# LCD_Connector.net
KiCad netlist of a schematic drawn in Altium Designer
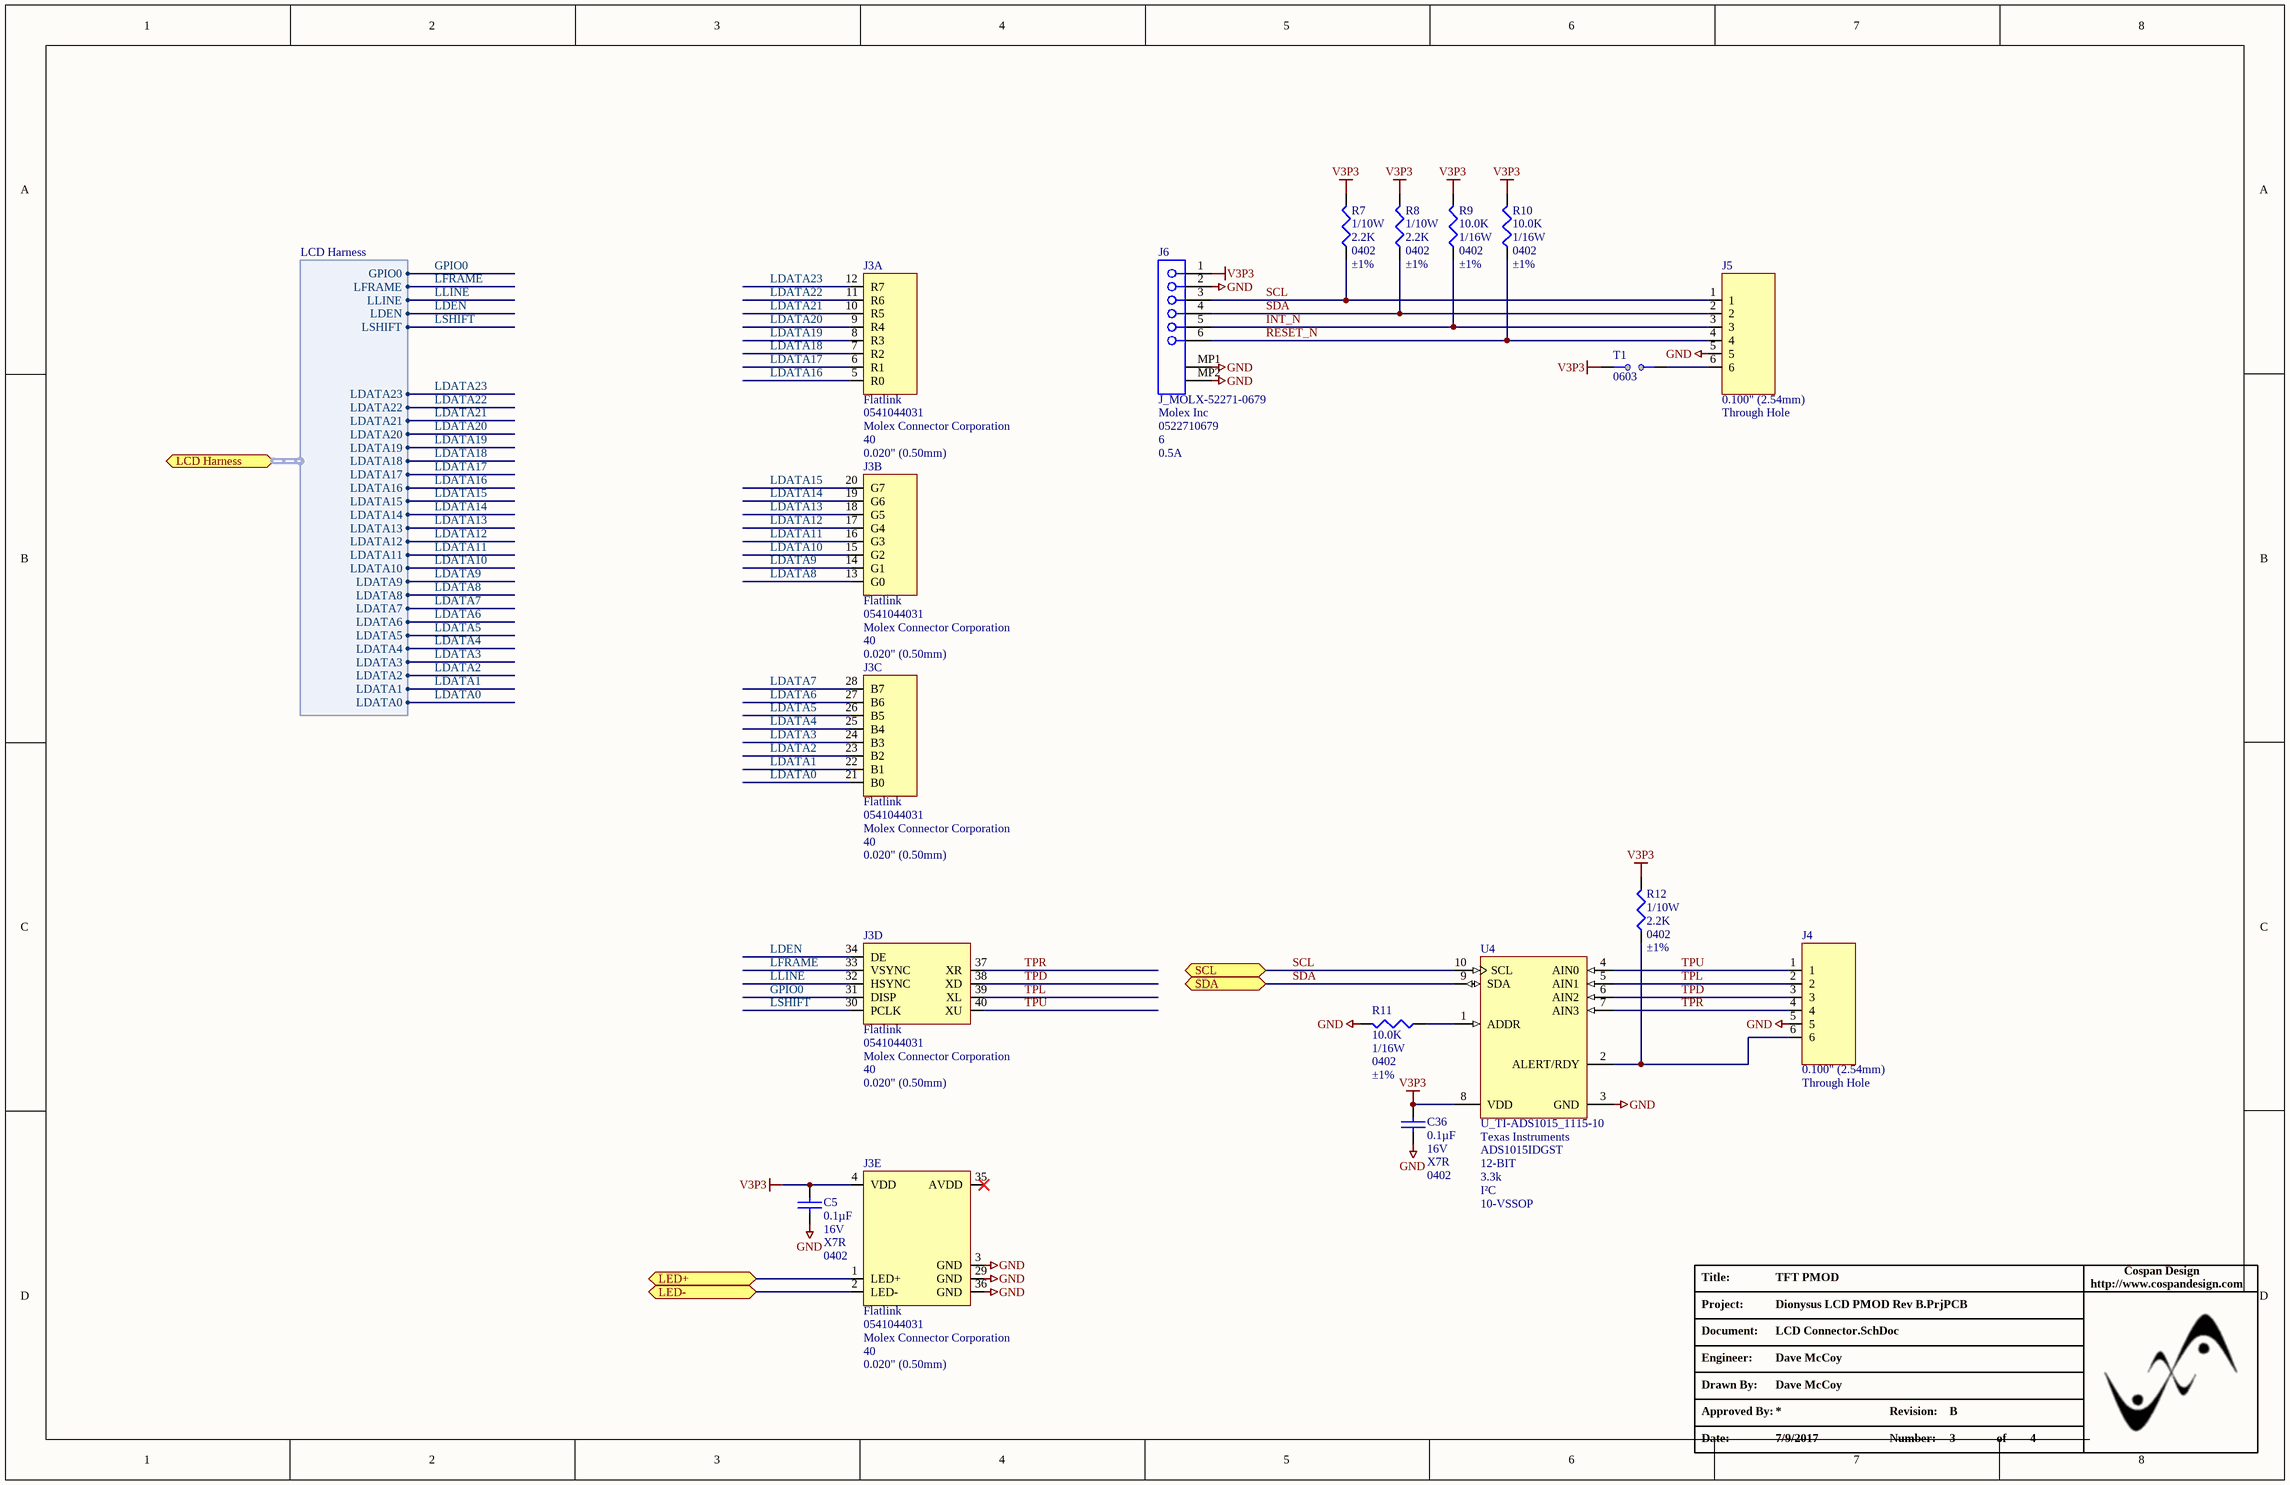
[diagram p0: LCD Connector.SchDoc]

(export (version "E")
  (design (tool "Eeschema 10.0.6"))
  (components
    (comp (ref "C5")
      (value "0.1uF")
      (footprint "C_0402")
      (description "CAP CER .10UF 16V X7R 0402")
      (fields
        (field (name "MANUFACTURER") "TDK Corporation")
        (field (name "MANUFACTURER PART NUMBER") "C1005X7R1C104K050BC")
        (field (name "CAPACITANCE") "0.1µF")
        (field (name "VOLTAGE - RATED") "16V")
        (field (name "TEMPERATURE COEFFICIENT") "X7R")
        (field (name "PACKAGE / CASE") "0402")
      )
      (libsource (lib "Main LibraryX") (part "C_0402_0.1UF_16V"))
    )
    (comp (ref "C36")
      (value "0.1uF")
      (footprint "C_0402")
      (description "CAP CER .10UF 16V X7R 0402")
      (fields
        (field (name "MANUFACTURER") "TDK Corporation")
        (field (name "MANUFACTURER PART NUMBER") "C1005X7R1C104K050BC")
        (field (name "CAPACITANCE") "0.1µF")
        (field (name "VOLTAGE - RATED") "16V")
        (field (name "TEMPERATURE COEFFICIENT") "X7R")
        (field (name "PACKAGE / CASE") "0402")
      )
      (libsource (lib "Main LibraryX") (part "C_0402_0.1UF_16V"))
    )
    (comp (ref "J3")
      (value "Flatlink")
      (footprint "FPC_40PIN")
      (description "CONN FFC/FPC .50MM 40POS R/A SMD")
      (fields
        (field (name "MANUFACTURER PART NUMBER") "0541044031")
        (field (name "MANUFACTURER") "Molex Connector Corporation")
        (field (name "NUMBER OF POSITIONS") "40")
        (field (name "PITCH") "0.020\" (0.50mm)")
      )
      (libsource (lib "Main LibraryX") (part "J_FPC_MOLEX_40POS_TOP"))
    )
    (comp (ref "J4")
      (value "J_HDR1X6_THRHOLE_VERT_FEMALE")
      (footprint "HDR_1X6 - FEMALE")
      (description "CONN HEADER FEMALE 6POS .1\" TIN")
      (fields
        (field (name "MANUFACTURER") "Samtec")
        (field (name "MANUFACTURER PART NUMBER") "SSW-106-01-T-S")
        (field (name "PITCH") "0.100\" (2.54mm)")
        (field (name "MOUNTING TYPE") "Through Hole")
      )
      (libsource (lib "Main Library") (part "J_HDR1X6_THRHOLE_VERT_FEMALE"))
    )
    (comp (ref "J5")
      (value "J_HDR1X6_THRHOLE_VERT")
      (footprint "HDR_1X6")
      (description "CONN HEADER .100\" 12POS TIN PCB")
      (fields
        (field (name "MANUFACTURER") "Samtec")
        (field (name "MANUFACTURER PART NUMBER") "TSW-106-07-T-S")
        (field (name "PITCH") "0.100\" (2.54mm)")
        (field (name "MOUNTING TYPE") "Through Hole")
      )
      (libsource (lib "Main Library") (part "J_HDR1X6_THRHOLE_VERT"))
    )
    (comp (ref "J6")
      (value "J_MOLX-52271-0679")
      (footprint "MOLX-52271-0679")
      (description "CONN FFC 6POS 1MM R/A ZIF SMD")
      (fields
        (field (name "MANUFACTURER") "Molex Inc")
        (field (name "MANUFACTURER PART NUMBER") "0522710679")
        (field (name "NUMBER OF POSITIONS") "6")
        (field (name "CURRENT RATING") "0.5A")
      )
      (libsource (lib "Main Library") (part "J_MOLX-52271-0679"))
    )
    (comp (ref "R7")
      (value "2.2k Ohms")
      (footprint "R_0402")
      (description "RES 2.20K OHM 1/10W 1% 0402 SMD")
      (fields
        (field (name "MANUFACTURER") "Yageo")
        (field (name "MANUFACTURER PART NUMBER") "RC0402FR-072K2L")
        (field (name "POWER (WATTS)") "1/10W")
        (field (name "RESISTANCE IN OHMS") "2.2K")
        (field (name "CASE") "0402")
        (field (name "TOLERANCE") "±1%")
      )
      (libsource (lib "Main Library") (part "R_0402_2.2K"))
    )
    (comp (ref "R8")
      (value "2.2k Ohms")
      (footprint "R_0402")
      (description "RES 2.20K OHM 1/10W 1% 0402 SMD")
      (fields
        (field (name "MANUFACTURER") "Yageo")
        (field (name "MANUFACTURER PART NUMBER") "RC0402FR-072K2L")
        (field (name "POWER (WATTS)") "1/10W")
        (field (name "RESISTANCE IN OHMS") "2.2K")
        (field (name "CASE") "0402")
        (field (name "TOLERANCE") "±1%")
      )
      (libsource (lib "Main Library") (part "R_0402_2.2K"))
    )
    (comp (ref "R9")
      (value "R_0402_10.0K")
      (footprint "R_0402")
      (description "RES 10.0K OHM 1/16W 1% 0402 SMD")
      (fields
        (field (name "MANUFACTURER") "Stackpole Electronics Inc")
        (field (name "MANUFACTURER PART NUMBER") "RMCF0402FT10K0")
        (field (name "RESISTANCE IN OHMS") "10.0K")
        (field (name "POWER (WATTS)") "1/16W")
        (field (name "CASE") "0402")
        (field (name "TOLERANCE") "±1%")
      )
      (libsource (lib "Cospan Design") (part "R_0402_10.0K"))
    )
    (comp (ref "R10")
      (value "R_0402_10.0K")
      (footprint "R_0402")
      (description "RES 10.0K OHM 1/16W 1% 0402 SMD")
      (fields
        (field (name "MANUFACTURER") "Stackpole Electronics Inc")
        (field (name "MANUFACTURER PART NUMBER") "RMCF0402FT10K0")
        (field (name "RESISTANCE IN OHMS") "10.0K")
        (field (name "POWER (WATTS)") "1/16W")
        (field (name "CASE") "0402")
        (field (name "TOLERANCE") "±1%")
      )
      (libsource (lib "Cospan Design") (part "R_0402_10.0K"))
    )
    (comp (ref "R11")
      (value "R_0402_10.0K")
      (footprint "R_0402")
      (description "RES 10.0K OHM 1/16W 1% 0402 SMD")
      (fields
        (field (name "MANUFACTURER") "Stackpole Electronics Inc")
        (field (name "MANUFACTURER PART NUMBER") "RMCF0402FT10K0")
        (field (name "RESISTANCE IN OHMS") "10.0K")
        (field (name "POWER (WATTS)") "1/16W")
        (field (name "CASE") "0402")
        (field (name "TOLERANCE") "±1%")
      )
      (libsource (lib "Cospan Design") (part "R_0402_10.0K"))
    )
    (comp (ref "R12")
      (value "2.2k Ohms")
      (footprint "R_0402")
      (description "RES 2.20K OHM 1/10W 1% 0402 SMD")
      (fields
        (field (name "MANUFACTURER") "Yageo")
        (field (name "MANUFACTURER PART NUMBER") "RC0402FR-072K2L")
        (field (name "POWER (WATTS)") "1/10W")
        (field (name "RESISTANCE IN OHMS") "2.2K")
        (field (name "CASE") "0402")
        (field (name "TOLERANCE") "±1%")
      )
      (libsource (lib "Main Library") (part "R_0402_2.2K"))
    )
    (comp (ref "T1")
      (value "Place Solder Bridge to Enable")
      (footprint "ERA-0603-SOLDER_JUMPER")
      (description "SOLDER_JUMPER PAD")
      (fields (field (name "CASE") "0603"))
      (libsource (lib "Main Library") (part "T_0603_JUMPER_PAD"))
    )
    (comp (ref "U4")
      (value "U_TI-ADS1015_1115-10")
      (footprint "TI-DGS10_L")
      (description "IC ADC 12BIT I2C W/REF 10-MSOP")
      (fields
        (field (name "MANUFACTURER") "Texas Instruments")
        (field (name "MANUFACTURER PART NUMBER") "ADS1015IDGST")
        (field (name "NUMBER OF BITS") "12-BIT")
        (field (name "SAMPLING RATE (PER SECOND)") "3.3k")
        (field (name "DATA INTERFACE") "I²C")
        (field (name "SUPPLIER DEVICE PACKAGE") "10-VSSOP")
      )
      (libsource (lib "Main LibraryX") (part "U_TI-ADS1015_1115-10"))
    )
  )
  (nets
    (net (code "3") (name "/GPIO0") (class "Default")
      (node (ref "J3") (pin "31") (pinfunction "DISP_31") (pintype "passive"))
    )
    (net (code "4") (name "/INT_N") (class "Default")
      (node (ref "J5") (pin "3") (pinfunction "3_3") (pintype "passive"))
      (node (ref "J6") (pin "5") (pinfunction "5_5") (pintype "passive"))
      (node (ref "R9") (pin "2") (pinfunction "2_2") (pintype "passive"))
    )
    (net (code "5") (name "/LDATA0") (class "Default")
      (node (ref "J3") (pin "21") (pinfunction "B0_21") (pintype "passive"))
    )
    (net (code "6") (name "/LDATA1") (class "Default")
      (node (ref "J3") (pin "22") (pinfunction "B1_22") (pintype "passive"))
    )
    (net (code "7") (name "/LDATA2") (class "Default")
      (node (ref "J3") (pin "23") (pinfunction "B2_23") (pintype "passive"))
    )
    (net (code "8") (name "/LDATA3") (class "Default")
      (node (ref "J3") (pin "24") (pinfunction "B3_24") (pintype "passive"))
    )
    (net (code "9") (name "/LDATA4") (class "Default")
      (node (ref "J3") (pin "25") (pinfunction "B4_25") (pintype "passive"))
    )
    (net (code "10") (name "/LDATA5") (class "Default")
      (node (ref "J3") (pin "26") (pinfunction "B5_26") (pintype "passive"))
    )
    (net (code "11") (name "/LDATA6") (class "Default")
      (node (ref "J3") (pin "27") (pinfunction "B6_27") (pintype "passive"))
    )
    (net (code "12") (name "/LDATA7") (class "Default")
      (node (ref "J3") (pin "28") (pinfunction "B7_28") (pintype "passive"))
    )
    (net (code "13") (name "/LDATA8") (class "Default")
      (node (ref "J3") (pin "13") (pinfunction "G0_13") (pintype "passive"))
    )
    (net (code "14") (name "/LDATA9") (class "Default")
      (node (ref "J3") (pin "14") (pinfunction "G1_14") (pintype "passive"))
    )
    (net (code "15") (name "/LDATA10") (class "Default")
      (node (ref "J3") (pin "15") (pinfunction "G2_15") (pintype "passive"))
    )
    (net (code "16") (name "/LDATA11") (class "Default")
      (node (ref "J3") (pin "16") (pinfunction "G3_16") (pintype "passive"))
    )
    (net (code "17") (name "/LDATA12") (class "Default")
      (node (ref "J3") (pin "17") (pinfunction "G4_17") (pintype "passive"))
    )
    (net (code "18") (name "/LDATA13") (class "Default")
      (node (ref "J3") (pin "18") (pinfunction "G5_18") (pintype "passive"))
    )
    (net (code "19") (name "/LDATA14") (class "Default")
      (node (ref "J3") (pin "19") (pinfunction "G6_19") (pintype "passive"))
    )
    (net (code "20") (name "/LDATA15") (class "Default")
      (node (ref "J3") (pin "20") (pinfunction "G7_20") (pintype "passive"))
    )
    (net (code "21") (name "/LDATA16") (class "Default")
      (node (ref "J3") (pin "5") (pinfunction "R0_5") (pintype "passive"))
    )
    (net (code "22") (name "/LDATA17") (class "Default")
      (node (ref "J3") (pin "6") (pinfunction "R1_6") (pintype "passive"))
    )
    (net (code "23") (name "/LDATA18") (class "Default")
      (node (ref "J3") (pin "7") (pinfunction "R2_7") (pintype "passive"))
    )
    (net (code "24") (name "/LDATA19") (class "Default")
      (node (ref "J3") (pin "8") (pinfunction "R3_8") (pintype "passive"))
    )
    (net (code "25") (name "/LDATA20") (class "Default")
      (node (ref "J3") (pin "9") (pinfunction "R4_9") (pintype "passive"))
    )
    (net (code "26") (name "/LDATA21") (class "Default")
      (node (ref "J3") (pin "10") (pinfunction "R5_10") (pintype "passive"))
    )
    (net (code "27") (name "/LDATA22") (class "Default")
      (node (ref "J3") (pin "11") (pinfunction "R6_11") (pintype "passive"))
    )
    (net (code "28") (name "/LDATA23") (class "Default")
      (node (ref "J3") (pin "12") (pinfunction "R7_12") (pintype "passive"))
    )
    (net (code "29") (name "/LDEN") (class "Default")
      (node (ref "J3") (pin "34") (pinfunction "DE_34") (pintype "passive"))
    )
    (net (code "30") (name "/LED+") (class "Default")
      (node (ref "J3") (pin "1") (pinfunction "LED+_1") (pintype "passive"))
    )
    (net (code "31") (name "/LED-") (class "Default")
      (node (ref "J3") (pin "2") (pinfunction "LED-_2") (pintype "passive"))
    )
    (net (code "32") (name "/LFRAME") (class "Default")
      (node (ref "J3") (pin "33") (pinfunction "VSYNC_33") (pintype "passive"))
    )
    (net (code "33") (name "/LLINE") (class "Default")
      (node (ref "J3") (pin "32") (pinfunction "HSYNC_32") (pintype "passive"))
    )
    (net (code "34") (name "/LSHIFT") (class "Default")
      (node (ref "J3") (pin "30") (pinfunction "PCLK_30") (pintype "passive"))
    )
    (net (code "35") (name "/RESET_N") (class "Default")
      (node (ref "J5") (pin "4") (pinfunction "4_4") (pintype "passive"))
      (node (ref "J6") (pin "6") (pinfunction "6_6") (pintype "passive"))
      (node (ref "R10") (pin "2") (pinfunction "2_2") (pintype "passive"))
    )
    (net (code "36") (name "/SCL") (class "Default")
      (node (ref "J5") (pin "1") (pinfunction "1_1") (pintype "passive"))
      (node (ref "J6") (pin "3") (pinfunction "3_3") (pintype "passive"))
      (node (ref "R7") (pin "2") (pinfunction "2_2") (pintype "passive"))
      (node (ref "U4") (pin "10") (pinfunction "SCL_10") (pintype "input"))
    )
    (net (code "37") (name "/SDA") (class "Default")
      (node (ref "J5") (pin "2") (pinfunction "2_2") (pintype "passive"))
      (node (ref "J6") (pin "4") (pinfunction "4_4") (pintype "passive"))
      (node (ref "R8") (pin "2") (pinfunction "2_2") (pintype "passive"))
      (node (ref "U4") (pin "9") (pinfunction "SDA_9") (pintype "bidirectional"))
    )
    (net (code "38") (name "/TPD") (class "Default")
      (node (ref "J3") (pin "38") (pinfunction "XD_38") (pintype "passive"))
      (node (ref "J4") (pin "3") (pinfunction "3_3") (pintype "passive"))
      (node (ref "U4") (pin "6") (pinfunction "AIN2_6") (pintype "input"))
    )
    (net (code "39") (name "/TPL") (class "Default")
      (node (ref "J3") (pin "39") (pinfunction "XL_39") (pintype "passive"))
      (node (ref "J4") (pin "2") (pinfunction "2_2") (pintype "passive"))
      (node (ref "U4") (pin "5") (pinfunction "AIN1_5") (pintype "input"))
    )
    (net (code "40") (name "/TPR") (class "Default")
      (node (ref "J3") (pin "37") (pinfunction "XR_37") (pintype "passive"))
      (node (ref "J4") (pin "4") (pinfunction "4_4") (pintype "passive"))
      (node (ref "U4") (pin "7") (pinfunction "AIN3_7") (pintype "input"))
    )
    (net (code "41") (name "/TPU") (class "Default")
      (node (ref "J3") (pin "40") (pinfunction "XU_40") (pintype "passive"))
      (node (ref "J4") (pin "1") (pinfunction "1_1") (pintype "passive"))
      (node (ref "U4") (pin "4") (pinfunction "AIN0_4") (pintype "input"))
    )
    (net (code "43") (name "GND") (class "Default")
      (node (ref "C36") (pin "1") (pinfunction "1_1") (pintype "passive"))
      (node (ref "C5") (pin "1") (pinfunction "1_1") (pintype "passive"))
      (node (ref "J3") (pin "29") (pinfunction "GND_29") (pintype "passive"))
      (node (ref "J3") (pin "3") (pinfunction "GND_3") (pintype "passive"))
      (node (ref "J3") (pin "36") (pinfunction "GND_36") (pintype "passive"))
      (node (ref "J4") (pin "5") (pinfunction "5_5") (pintype "passive"))
      (node (ref "J5") (pin "5") (pinfunction "5_5") (pintype "passive"))
      (node (ref "J6") (pin "2") (pinfunction "2_2") (pintype "passive"))
      (node (ref "J6") (pin "MP1") (pinfunction "MP1_MP1") (pintype "passive"))
      (node (ref "J6") (pin "MP2") (pinfunction "MP2_MP2") (pintype "passive"))
      (node (ref "R11") (pin "1") (pinfunction "1_1") (pintype "passive"))
      (node (ref "U4") (pin "3") (pinfunction "GND_3") (pintype "power_in"))
    )
    (net (code "44") (name "Net-(J5-Pad6)") (class "Default")
      (node (ref "J5") (pin "6") (pinfunction "6_6") (pintype "passive"))
      (node (ref "T1") (pin "2") (pinfunction "2_2") (pintype "passive"))
    )
    (net (code "45") (name "Net-(U4-ADDR)") (class "Default")
      (node (ref "R11") (pin "2") (pinfunction "2_2") (pintype "passive"))
      (node (ref "U4") (pin "1") (pinfunction "ADDR_1") (pintype "input"))
    )
    (net (code "46") (name "Net-(U4-ALERT{slash}RDY)") (class "Default")
      (node (ref "J4") (pin "6") (pinfunction "6_6") (pintype "passive"))
      (node (ref "R12") (pin "2") (pinfunction "2_2") (pintype "passive"))
      (node (ref "U4") (pin "2") (pinfunction "ALERT/RDY_2") (pintype "open_collector"))
    )
    (net (code "47") (name "V3P3") (class "Default")
      (node (ref "C36") (pin "2") (pinfunction "2_2") (pintype "passive"))
      (node (ref "C5") (pin "2") (pinfunction "2_2") (pintype "passive"))
      (node (ref "J3") (pin "4") (pinfunction "VDD_4") (pintype "passive"))
      (node (ref "J6") (pin "1") (pinfunction "1_1") (pintype "passive"))
      (node (ref "R10") (pin "1") (pinfunction "1_1") (pintype "passive"))
      (node (ref "R12") (pin "1") (pinfunction "1_1") (pintype "passive"))
      (node (ref "R7") (pin "1") (pinfunction "1_1") (pintype "passive"))
      (node (ref "R8") (pin "1") (pinfunction "1_1") (pintype "passive"))
      (node (ref "R9") (pin "1") (pinfunction "1_1") (pintype "passive"))
      (node (ref "T1") (pin "1") (pinfunction "1_1") (pintype "passive"))
      (node (ref "U4") (pin "8") (pinfunction "VDD_8") (pintype "power_in"))
    )
    (net (code "48") (name "unconnected-(J3E-AVDD-Pad35)") (class "Default")
      (node (ref "J3") (pin "35") (pinfunction "AVDD_35") (pintype "passive+no_connect"))
    )
  )
)
